# DONGLE02.net
KiCad netlist of a schematic drawn in Altium Designer
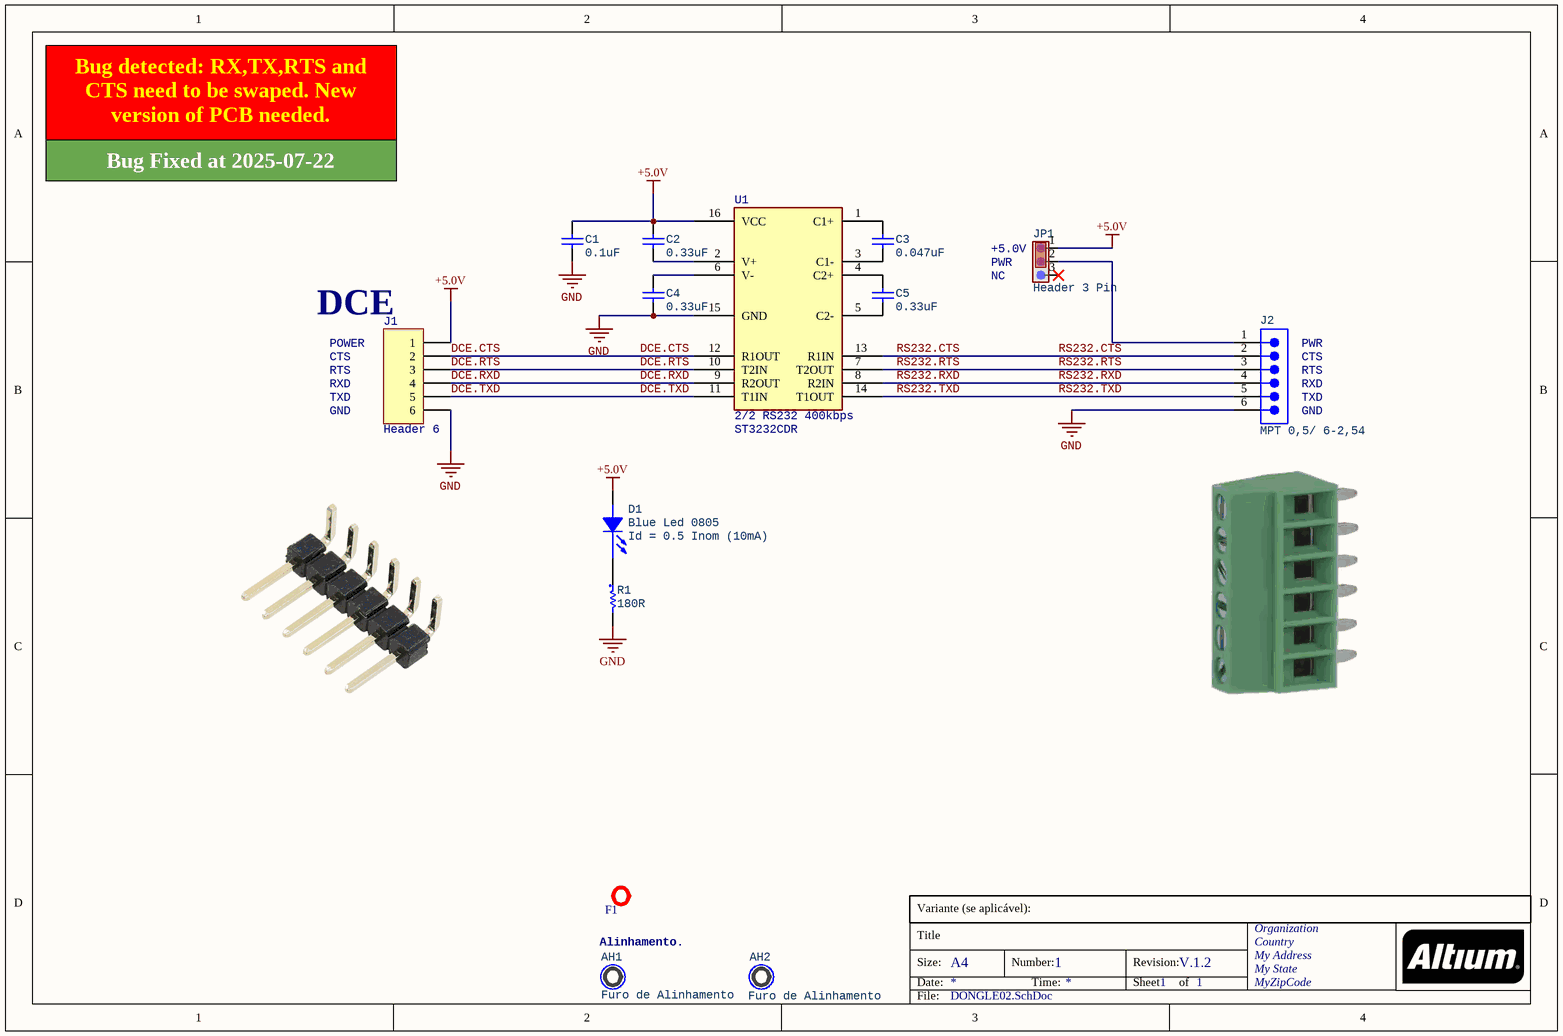
[diagram p0: DONGLE02.SchDoc]

(export (version "E")
  (design (tool "Eeschema 10.0.6"))
  (components
    (comp (ref "AH1")
      (value "Furo de Alinhamento")
      (footprint "AH_2.0MMD")
      (libsource (lib "My_Library") (part "Aligment Hole M2"))
    )
    (comp (ref "AH2")
      (value "Furo de Alinhamento")
      (footprint "AH_2.0MMD")
      (libsource (lib "My_Library") (part "Aligment Hole M2"))
    )
    (comp (ref "C1")
      (value "0.1uF")
      (footprint "C0805")
      (description "0.1 µF ±10% 100V Ceramic Capacitor X7R 0805 (2012 Metric)")
      (fields (field (name "MANUFACTURER") "Murata Electronics"))
      (libsource (lib "My_Library") (part "CAP"))
    )
    (comp (ref "C2")
      (value "0.33uF")
      (footprint "C0805")
      (description "0.33 µF ±5% 25V Ceramic Capacitor X7R 0805 (2012 Metric)")
      (fields (field (name "MANUFACTURER") "KEMET"))
      (libsource (lib "My_Library") (part "CAP"))
    )
    (comp (ref "C3")
      (value "0.047uF")
      (footprint "C0805")
      (description "0.047 µF ±5% 25V Ceramic Capacitor X7R 0805 (2012 Metric)")
      (fields (field (name "MANUFACTURER") "KYOCERA AVX"))
      (libsource (lib "My_Library") (part "CAP"))
    )
    (comp (ref "C4")
      (value "0.33uF")
      (footprint "C0805")
      (description "0.33 µF ±5% 25V Ceramic Capacitor X7R 0805 (2012 Metric)")
      (fields (field (name "MANUFACTURER") "KEMET"))
      (libsource (lib "My_Library") (part "CAP"))
    )
    (comp (ref "C5")
      (value "0.33uF")
      (footprint "C0805")
      (description "0.33 µF ±5% 25V Ceramic Capacitor X7R 0805 (2012 Metric)")
      (fields (field (name "MANUFACTURER") "KEMET"))
      (libsource (lib "My_Library") (part "CAP"))
    )
    (comp (ref "D1")
      (value "Blue Led 0805")
      (footprint "LED 0805")
      (description "Blue 470nm LED Indication - Discrete 3.2V 0805 (2012 Metric)")
      (fields (field (name "MANUFACTURER") "Würth Elektronik") (field (name "INFO") "Id = 0.5 Inom (10mA)"))
      (libsource (lib "My_Library") (part "LED GREEN 0805"))
    )
    (comp (ref "F1")
      (value "~")
      (footprint "FIDUCIAL")
      (description "FIDUCIAL MARK")
      (libsource (lib "My_Library") (part "FIDUCIAL"))
    )
    (comp (ref "J1")
      (value "Header 6")
      (footprint "BERG-M-6V-H-INV")
      (description "Connector Header Through Hole, Right Angle 6 position 0.100\" (2.54mm)")
      (fields (field (name "MANUFACTURER") "Adam Tech"))
      (libsource (lib "Miscellaneous Connectors") (part "Header 6"))
    )
    (comp (ref "J2")
      (value "MPT 0,5/ 6-2,54")
      (footprint "1725698")
      (description "6 Position Wire to Board Terminal Block Horizontal with Board 0.100\" (2.54mm) Through Hole")
      (fields (field (name "MANUFACTURER") "Phoenix Contact"))
      (libsource (lib "691101710002_Altium_WR-TBL_rev23c") (part "691322110006"))
    )
    (comp (ref "JP1")
      (value "Header 3 Pin")
      (footprint "JMP-3-PTH-180")
      (description "3 Pin Jumper")
      (fields (field (name "MANUFACTURER") "Würth Elektronik"))
      (libsource (lib "My_Library") (part "Jumper 3"))
    )
    (comp (ref "R1")
      (value "180R")
      (footprint "R0805")
      (description "180 Ohms ±1% 0.25W, 1/4W Chip Resistor 0805 (2012 Metric) Anti-Sulfur Thin Film")
      (fields (field (name "MANUFACTURER") "Stackpole Electronics Inc"))
      (libsource (lib "My_Library") (part "RESISTOR"))
    )
    (comp (ref "U1")
      (value "2/2 RS232 400kbps")
      (footprint "SOIC16N")
      (description "2/2 Transceiver Full RS232 16-SO")
      (fields
        (field (name "MANUFACTURER P/N") "ST3232CDR")
        (field (name "MANUFACTURER") "STMicroelectronics")
      )
      (libsource (lib "My_Library") (part "CI SMD ST3232CDR-SO16"))
    )
  )
  (nets
    (net (code "1") (name "+5.0V") (class "Default")
      (node (ref "C1") (pin "1") (pinfunction "1_1") (pintype "passive"))
      (node (ref "C2") (pin "1") (pinfunction "1_1") (pintype "passive"))
      (node (ref "D1") (pin "A") (pinfunction "A_A") (pintype "passive"))
      (node (ref "J1") (pin "1") (pinfunction "1_1") (pintype "passive"))
      (node (ref "JP1") (pin "1") (pinfunction "1_1") (pintype "passive"))
      (node (ref "U1") (pin "16") (pinfunction "VCC_16") (pintype "passive"))
    )
    (net (code "2") (name "/DCE.CTS") (class "Default")
      (node (ref "J1") (pin "2") (pinfunction "2_2") (pintype "passive"))
      (node (ref "U1") (pin "12") (pinfunction "R1OUT_12") (pintype "passive"))
    )
    (net (code "3") (name "/DCE.RTS") (class "Default")
      (node (ref "J1") (pin "3") (pinfunction "3_3") (pintype "passive"))
      (node (ref "U1") (pin "10") (pinfunction "T2IN_10") (pintype "passive"))
    )
    (net (code "4") (name "/DCE.RXD") (class "Default")
      (node (ref "J1") (pin "4") (pinfunction "4_4") (pintype "passive"))
      (node (ref "U1") (pin "9") (pinfunction "R2OUT_9") (pintype "passive"))
    )
    (net (code "5") (name "/DCE.TXD") (class "Default")
      (node (ref "J1") (pin "5") (pinfunction "5_5") (pintype "passive"))
      (node (ref "U1") (pin "11") (pinfunction "T1IN_11") (pintype "passive"))
    )
    (net (code "6") (name "/RS232.CTS") (class "Default")
      (node (ref "J2") (pin "2") (pinfunction "2_2") (pintype "passive"))
      (node (ref "U1") (pin "13") (pinfunction "R1IN_13") (pintype "passive"))
    )
    (net (code "7") (name "/RS232.RTS") (class "Default")
      (node (ref "J2") (pin "3") (pinfunction "3_3") (pintype "passive"))
      (node (ref "U1") (pin "7") (pinfunction "T2OUT_7") (pintype "passive"))
    )
    (net (code "8") (name "/RS232.RXD") (class "Default")
      (node (ref "J2") (pin "4") (pinfunction "4_4") (pintype "passive"))
      (node (ref "U1") (pin "8") (pinfunction "R2IN_8") (pintype "passive"))
    )
    (net (code "9") (name "/RS232.TXD") (class "Default")
      (node (ref "J2") (pin "5") (pinfunction "5_5") (pintype "passive"))
      (node (ref "U1") (pin "14") (pinfunction "T1OUT_14") (pintype "passive"))
    )
    (net (code "10") (name "GND") (class "Default")
      (node (ref "C1") (pin "2") (pinfunction "2_2") (pintype "passive"))
      (node (ref "C4") (pin "2") (pinfunction "2_2") (pintype "passive"))
      (node (ref "J1") (pin "6") (pinfunction "6_6") (pintype "passive"))
      (node (ref "J2") (pin "6") (pinfunction "6_6") (pintype "passive"))
      (node (ref "R1") (pin "2") (pinfunction "2_2") (pintype "passive"))
      (node (ref "U1") (pin "15") (pinfunction "GND_15") (pintype "passive"))
    )
    (net (code "11") (name "Net-(D1-PadK)") (class "Default")
      (node (ref "D1") (pin "K") (pinfunction "K_K") (pintype "passive"))
      (node (ref "R1") (pin "1") (pinfunction "1_1") (pintype "passive"))
    )
    (net (code "12") (name "Net-(J2-Pad1)") (class "Default")
      (node (ref "J2") (pin "1") (pinfunction "1_1") (pintype "passive"))
      (node (ref "JP1") (pin "2") (pinfunction "2_2") (pintype "passive"))
    )
    (net (code "13") (name "Net-(U1-C1+)") (class "Default")
      (node (ref "C3") (pin "1") (pinfunction "1_1") (pintype "passive"))
      (node (ref "U1") (pin "1") (pinfunction "C1+_1") (pintype "passive"))
    )
    (net (code "14") (name "Net-(U1-C1-)") (class "Default")
      (node (ref "C3") (pin "2") (pinfunction "2_2") (pintype "passive"))
      (node (ref "U1") (pin "3") (pinfunction "C1-_3") (pintype "passive"))
    )
    (net (code "15") (name "Net-(U1-C2+)") (class "Default")
      (node (ref "C5") (pin "1") (pinfunction "1_1") (pintype "passive"))
      (node (ref "U1") (pin "4") (pinfunction "C2+_4") (pintype "passive"))
    )
    (net (code "16") (name "Net-(U1-C2-)") (class "Default")
      (node (ref "C5") (pin "2") (pinfunction "2_2") (pintype "passive"))
      (node (ref "U1") (pin "5") (pinfunction "C2-_5") (pintype "passive"))
    )
    (net (code "17") (name "Net-(U1-V+)") (class "Default")
      (node (ref "C2") (pin "2") (pinfunction "2_2") (pintype "passive"))
      (node (ref "U1") (pin "2") (pinfunction "V+_2") (pintype "passive"))
    )
    (net (code "18") (name "Net-(U1-V-)") (class "Default")
      (node (ref "C4") (pin "1") (pinfunction "1_1") (pintype "passive"))
      (node (ref "U1") (pin "6") (pinfunction "V-_6") (pintype "passive"))
    )
    (net (code "19") (name "unconnected-(JP1-Pad3)") (class "Default")
      (node (ref "JP1") (pin "3") (pinfunction "3_3") (pintype "passive+no_connect"))
    )
  )
)
